# clockport_nic.net
KiCad netlist of a schematic drawn in EAGLE
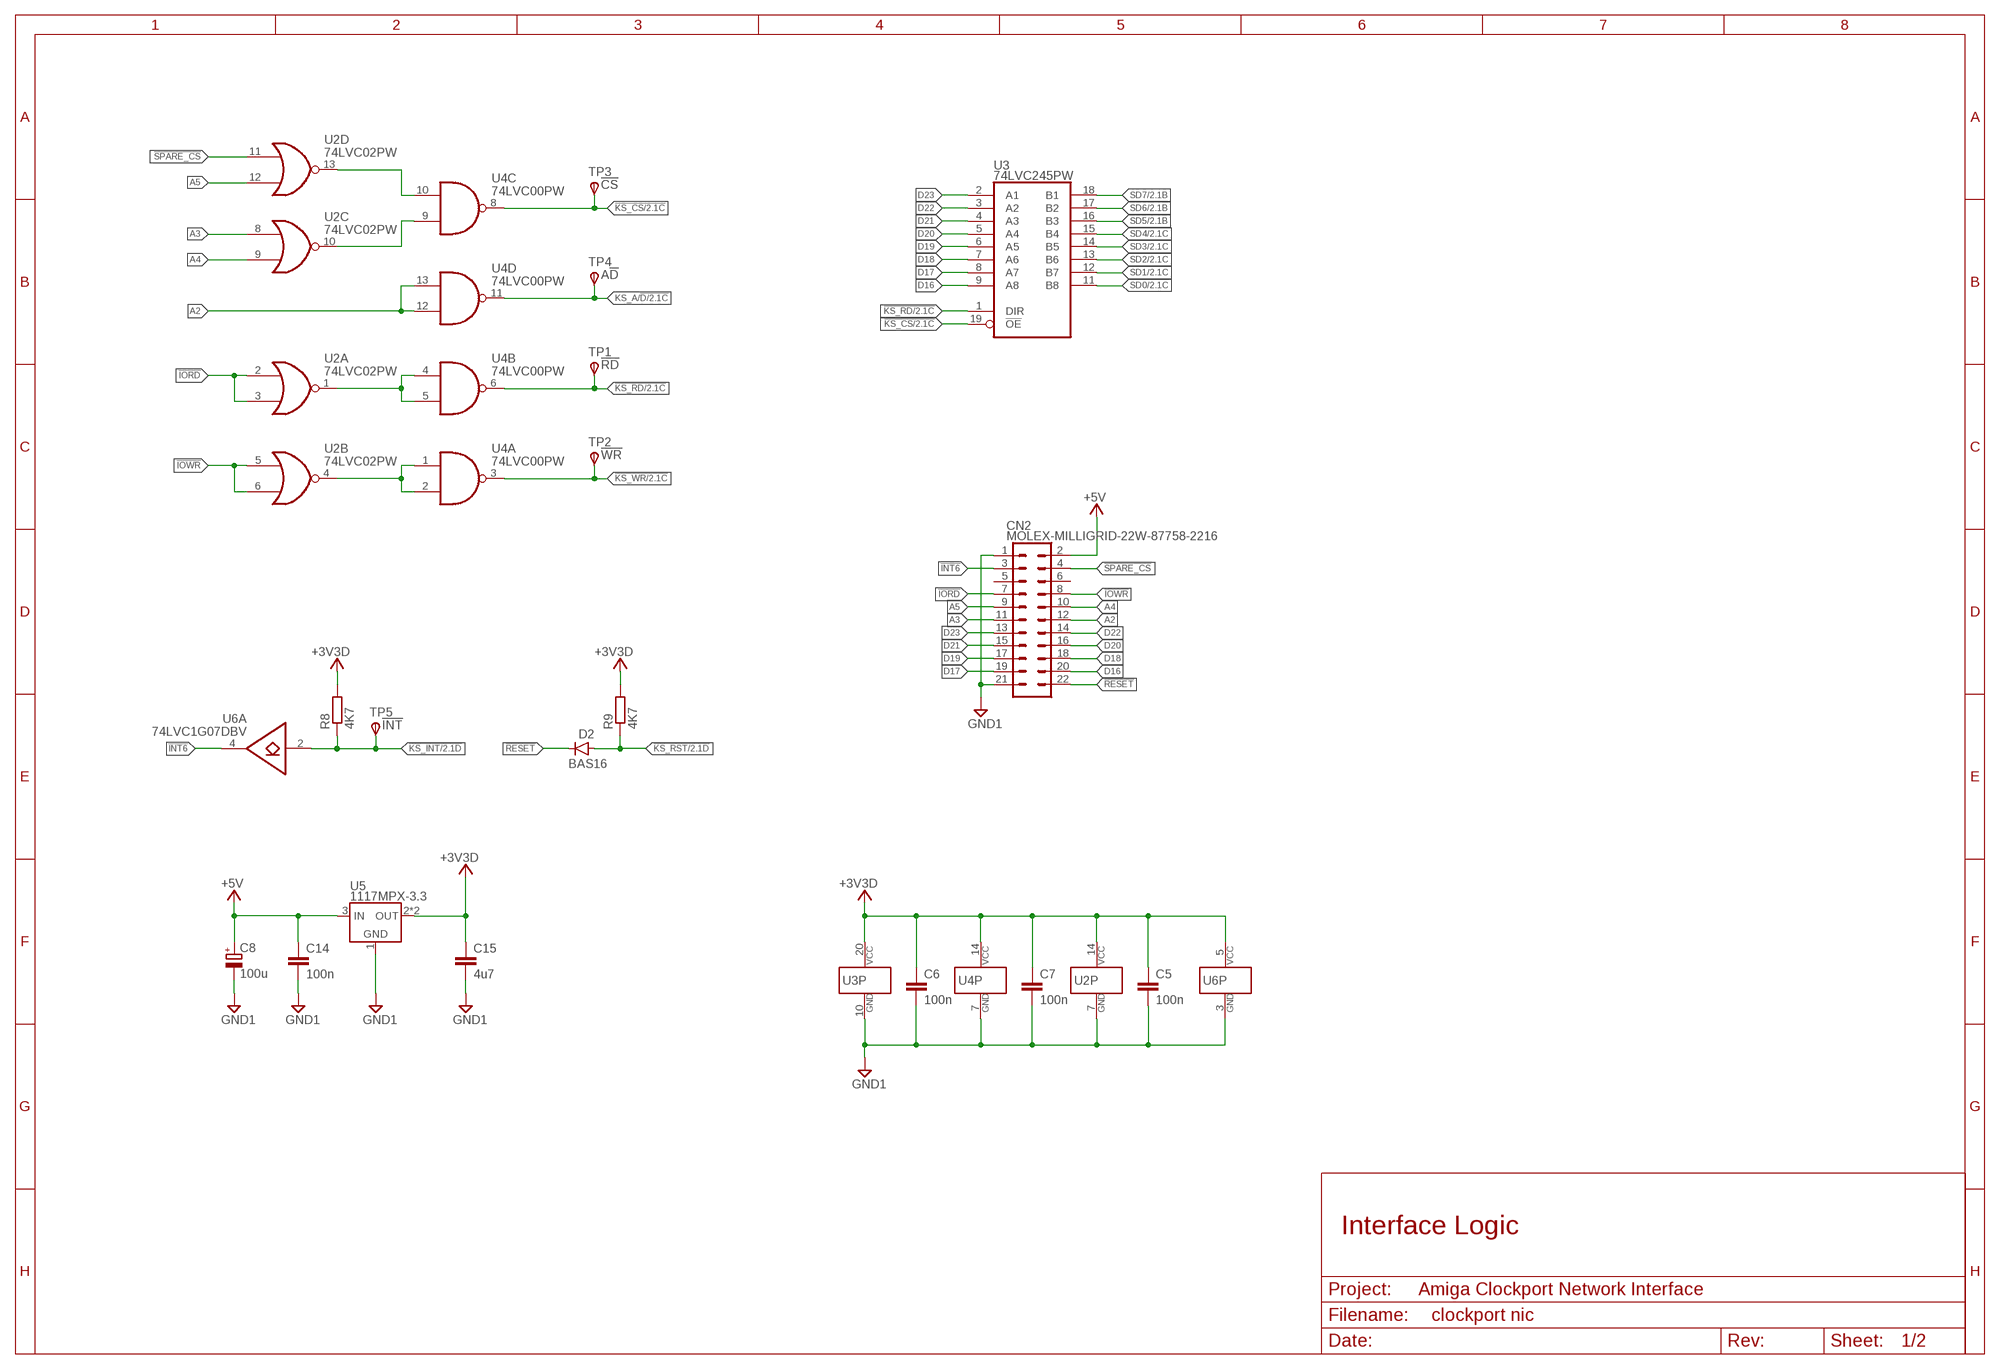
[diagram p0: schematic, sheet 1]
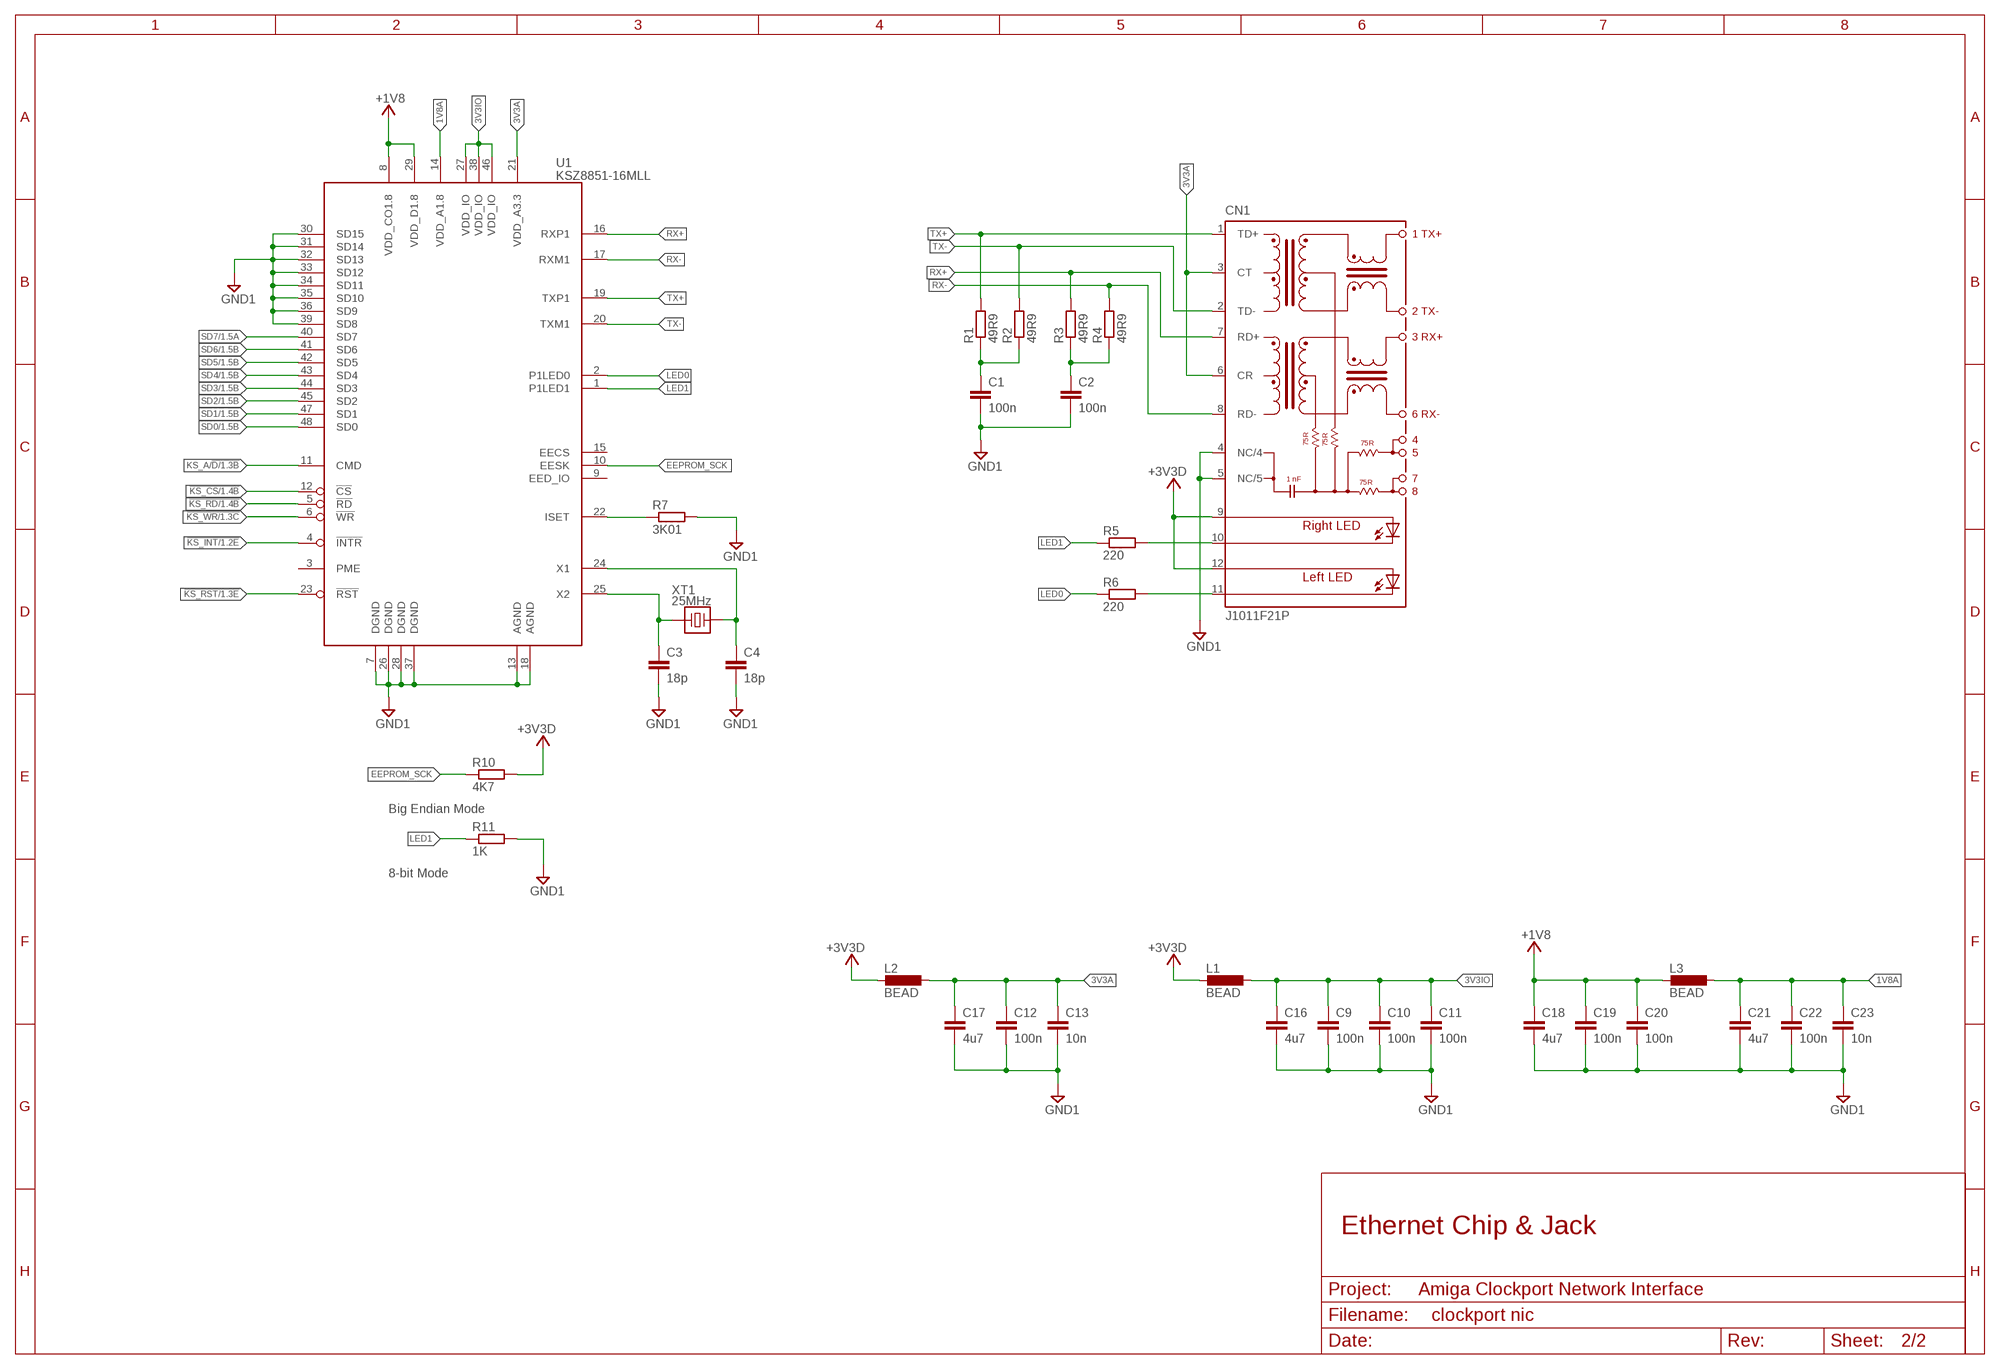
[diagram p1: schematic, sheet 2]

(export (version "E")
  (design (tool "Eeschema 10.0.6"))
  (components
    (comp (ref "C5")
      (value "100n")
      (footprint "eagle-import:C0603")
      (libsource (lib "eagle-import") (part "C-EUC0603"))
    )
    (comp (ref "C6")
      (value "100n")
      (footprint "eagle-import:C0603")
      (libsource (lib "eagle-import") (part "C-EUC0603"))
    )
    (comp (ref "C7")
      (value "100n")
      (footprint "eagle-import:C0603")
      (libsource (lib "eagle-import") (part "C-EUC0603"))
    )
    (comp (ref "C8")
      (value "100u")
      (footprint "eagle-import:E2,5-6")
      (libsource (lib "eagle-import") (part "CPOL-EUE2.5-6"))
    )
    (comp (ref "C14")
      (value "100n")
      (footprint "eagle-import:C0603")
      (libsource (lib "eagle-import") (part "C-EUC0603"))
    )
    (comp (ref "C15")
      (value "4u7")
      (footprint "eagle-import:C0805")
      (libsource (lib "eagle-import") (part "C-EUC0805"))
    )
    (comp (ref "CN2")
      (value "MOLEX-MILLIGRID-22W-87758-2216")
      (footprint "eagle-import:MOLEX-87758-2216")
      (libsource (lib "eagle-import") (part "MOLEX-MILLIGRID-22W-?87758-2216"))
    )
    (comp (ref "D2")
      (value "BAS16")
      (footprint "eagle-import:SOD323-R")
      (libsource (lib "eagle-import") (part "-DIODE_?SOD-323"))
    )
    (comp (ref "R8")
      (value "4K7")
      (footprint "eagle-import:R0603")
      (libsource (lib "eagle-import") (part "R-EU_R0603"))
    )
    (comp (ref "R9")
      (value "4K7")
      (footprint "eagle-import:R0603")
      (libsource (lib "eagle-import") (part "R-EU_R0603"))
    )
    (comp (ref "TP1")
      (value "TPSB1,27")
      (footprint "eagle-import:B1,27")
      (fields (field (name "TP_SIGNAL_NAME") "!RD"))
      (libsource (lib "eagle-import") (part "TPSB1,27"))
    )
    (comp (ref "TP2")
      (value "TPSB1,27")
      (footprint "eagle-import:B1,27")
      (fields (field (name "TP_SIGNAL_NAME") "!WR"))
      (libsource (lib "eagle-import") (part "TPSB1,27"))
    )
    (comp (ref "TP3")
      (value "TPSB1,27")
      (footprint "eagle-import:B1,27")
      (fields (field (name "TP_SIGNAL_NAME") "!CS"))
      (libsource (lib "eagle-import") (part "TPSB1,27"))
    )
    (comp (ref "TP4")
      (value "TPSB1,27")
      (footprint "eagle-import:B1,27")
      (fields (field (name "TP_SIGNAL_NAME") "A!D"))
      (libsource (lib "eagle-import") (part "TPSB1,27"))
    )
    (comp (ref "TP5")
      (value "TPSB1,27")
      (footprint "eagle-import:B1,27")
      (fields (field (name "TP_SIGNAL_NAME") "!INT"))
      (libsource (lib "eagle-import") (part "TPSB1,27"))
    )
    (comp (ref "U2")
      (value "74LVC02PW")
      (footprint "eagle-import:TSSOP14")
      (libsource (lib "eagle-import") (part "7402PWLVC"))
    )
    (comp (ref "U3")
      (value "74LVC245PW")
      (footprint "eagle-import:TSSOP20")
      (libsource (lib "eagle-import") (part "74245PWLVC"))
    )
    (comp (ref "U4")
      (value "74LVC00PW")
      (footprint "eagle-import:TSSOP14")
      (libsource (lib "eagle-import") (part "7400PWLVC"))
    )
    (comp (ref "U5")
      (value "1117MPX-3.3")
      (footprint "eagle-import:SOT223")
      (libsource (lib "eagle-import") (part "1117?-MPX3.3"))
    )
    (comp (ref "U6")
      (value "74LVC1G07DBV")
      (footprint "eagle-import:SOT23-5")
      (libsource (lib "eagle-import") (part "74LVC1G07DBV"))
    )
    (comp (ref "C1")
      (value "100n")
      (footprint "eagle-import:C0603")
      (libsource (lib "eagle-import") (part "C-EUC0603"))
    )
    (comp (ref "C2")
      (value "100n")
      (footprint "eagle-import:C0603")
      (libsource (lib "eagle-import") (part "C-EUC0603"))
    )
    (comp (ref "C3")
      (value "18p")
      (footprint "eagle-import:C0603")
      (libsource (lib "eagle-import") (part "C-EUC0603"))
    )
    (comp (ref "C4")
      (value "18p")
      (footprint "eagle-import:C0603")
      (libsource (lib "eagle-import") (part "C-EUC0603"))
    )
    (comp (ref "C9")
      (value "100n")
      (footprint "eagle-import:C0603")
      (libsource (lib "eagle-import") (part "C-EUC0603"))
    )
    (comp (ref "C10")
      (value "100n")
      (footprint "eagle-import:C0603")
      (libsource (lib "eagle-import") (part "C-EUC0603"))
    )
    (comp (ref "C11")
      (value "100n")
      (footprint "eagle-import:C0603")
      (libsource (lib "eagle-import") (part "C-EUC0603"))
    )
    (comp (ref "C12")
      (value "100n")
      (footprint "eagle-import:C0603")
      (libsource (lib "eagle-import") (part "C-EUC0603"))
    )
    (comp (ref "C13")
      (value "10n")
      (footprint "eagle-import:C0603")
      (libsource (lib "eagle-import") (part "C-EUC0603"))
    )
    (comp (ref "C16")
      (value "4u7")
      (footprint "eagle-import:C0805")
      (libsource (lib "eagle-import") (part "C-EUC0805"))
    )
    (comp (ref "C17")
      (value "4u7")
      (footprint "eagle-import:C0805")
      (libsource (lib "eagle-import") (part "C-EUC0805"))
    )
    (comp (ref "C18")
      (value "4u7")
      (footprint "eagle-import:C0805")
      (libsource (lib "eagle-import") (part "C-EUC0805"))
    )
    (comp (ref "C19")
      (value "100n")
      (footprint "eagle-import:C0603")
      (libsource (lib "eagle-import") (part "C-EUC0603"))
    )
    (comp (ref "C20")
      (value "100n")
      (footprint "eagle-import:C0603")
      (libsource (lib "eagle-import") (part "C-EUC0603"))
    )
    (comp (ref "C21")
      (value "4u7")
      (footprint "eagle-import:C0805")
      (libsource (lib "eagle-import") (part "C-EUC0805"))
    )
    (comp (ref "C22")
      (value "100n")
      (footprint "eagle-import:C0603")
      (libsource (lib "eagle-import") (part "C-EUC0603"))
    )
    (comp (ref "C23")
      (value "10n")
      (footprint "eagle-import:C0603")
      (libsource (lib "eagle-import") (part "C-EUC0603"))
    )
    (comp (ref "CN1")
      (value "J1011F21P")
      (footprint "eagle-import:J1")
      (libsource (lib "eagle-import") (part "J1011F21P"))
    )
    (comp (ref "L1")
      (value "BEAD")
      (footprint "eagle-import:L2012C")
      (libsource (lib "eagle-import") (part "L-EUL2012C"))
    )
    (comp (ref "L2")
      (value "BEAD")
      (footprint "eagle-import:L2012C")
      (libsource (lib "eagle-import") (part "L-EUL2012C"))
    )
    (comp (ref "L3")
      (value "BEAD")
      (footprint "eagle-import:L2012C")
      (libsource (lib "eagle-import") (part "L-EUL2012C"))
    )
    (comp (ref "R1")
      (value "49R9")
      (footprint "eagle-import:R0603")
      (libsource (lib "eagle-import") (part "R-EU_R0603"))
    )
    (comp (ref "R2")
      (value "49R9")
      (footprint "eagle-import:R0603")
      (libsource (lib "eagle-import") (part "R-EU_R0603"))
    )
    (comp (ref "R3")
      (value "49R9")
      (footprint "eagle-import:R0603")
      (libsource (lib "eagle-import") (part "R-EU_R0603"))
    )
    (comp (ref "R4")
      (value "49R9")
      (footprint "eagle-import:R0603")
      (libsource (lib "eagle-import") (part "R-EU_R0603"))
    )
    (comp (ref "R5")
      (value "220")
      (footprint "eagle-import:R0603")
      (libsource (lib "eagle-import") (part "R-EU_R0603"))
    )
    (comp (ref "R6")
      (value "220")
      (footprint "eagle-import:R0603")
      (libsource (lib "eagle-import") (part "R-EU_R0603"))
    )
    (comp (ref "R7")
      (value "3K01")
      (footprint "eagle-import:R0603")
      (libsource (lib "eagle-import") (part "R-EU_R0603"))
    )
    (comp (ref "R10")
      (value "4K7")
      (footprint "eagle-import:R0603")
      (libsource (lib "eagle-import") (part "R-EU_R0603"))
    )
    (comp (ref "R11")
      (value "1K")
      (footprint "eagle-import:R0603")
      (libsource (lib "eagle-import") (part "R-EU_R0603"))
    )
    (comp (ref "U1")
      (value "KSZ8851-16MLL")
      (footprint "eagle-import:LQFP48")
      (libsource (lib "eagle-import") (part "KSZ8851-16MLL"))
    )
    (comp (ref "XT1")
      (value "25MHz")
      (footprint "eagle-import:3225_4PAD")
      (libsource (lib "eagle-import") (part "XTAL_3225"))
    )
  )
  (nets
    (net (code "1") (name "+1V8") (class "Default")
      (node (ref "C18") (pin "1") (pinfunction "1_1") (pintype "passive"))
      (node (ref "C19") (pin "1") (pinfunction "1_1") (pintype "passive"))
      (node (ref "C20") (pin "1") (pinfunction "1_1") (pintype "passive"))
      (node (ref "L3") (pin "2") (pinfunction "2_2") (pintype "passive"))
      (node (ref "U1") (pin "29") (pinfunction "VDD_D1.8_29") (pintype "power_in"))
      (node (ref "U1") (pin "8") (pinfunction "VDD_CO1.8_8") (pintype "output"))
    )
    (net (code "2") (name "+3V3D") (class "Default")
      (node (ref "C15") (pin "1") (pinfunction "1_1") (pintype "passive"))
      (node (ref "C5") (pin "1") (pinfunction "1_1") (pintype "passive"))
      (node (ref "C6") (pin "1") (pinfunction "1_1") (pintype "passive"))
      (node (ref "C7") (pin "1") (pinfunction "1_1") (pintype "passive"))
      (node (ref "CN1") (pin "12") (pinfunction "AL_12") (pintype "passive"))
      (node (ref "CN1") (pin "9") (pinfunction "A-R_9") (pintype "passive"))
      (node (ref "L1") (pin "2") (pinfunction "2_2") (pintype "passive"))
      (node (ref "L2") (pin "2") (pinfunction "2_2") (pintype "passive"))
      (node (ref "R10") (pin "2") (pinfunction "2_2") (pintype "passive"))
      (node (ref "R8") (pin "2") (pinfunction "2_2") (pintype "passive"))
      (node (ref "R9") (pin "2") (pinfunction "2_2") (pintype "passive"))
      (node (ref "U2") (pin "14") (pinfunction "VCC_14") (pintype "power_in"))
      (node (ref "U3") (pin "20") (pinfunction "VCC_20") (pintype "power_in"))
      (node (ref "U4") (pin "14") (pinfunction "VCC_14") (pintype "power_in"))
      (node (ref "U5") (pin "2") (pinfunction "OUT_2") (pintype "passive"))
      (node (ref "U5") (pin "4") (pinfunction "OUT_4") (pintype "passive"))
      (node (ref "U6") (pin "5") (pinfunction "VCC_5") (pintype "power_in"))
    )
    (net (code "3") (name "+5V") (class "Default")
      (node (ref "C14") (pin "1") (pinfunction "1_1") (pintype "passive"))
      (node (ref "C8") (pin "+") (pinfunction "+_+") (pintype "passive"))
      (node (ref "CN2") (pin "2") (pinfunction "2_2") (pintype "passive"))
      (node (ref "U5") (pin "3") (pinfunction "IN_3") (pintype "passive"))
    )
    (net (code "4") (name "1V8A") (class "Default")
      (node (ref "C21") (pin "1") (pinfunction "1_1") (pintype "passive"))
      (node (ref "C22") (pin "1") (pinfunction "1_1") (pintype "passive"))
      (node (ref "C23") (pin "1") (pinfunction "1_1") (pintype "passive"))
      (node (ref "L3") (pin "1") (pinfunction "1_1") (pintype "passive"))
      (node (ref "U1") (pin "14") (pinfunction "VDD_A1.8_14") (pintype "power_in"))
    )
    (net (code "5") (name "3V3A") (class "Default")
      (node (ref "C12") (pin "1") (pinfunction "1_1") (pintype "passive"))
      (node (ref "C13") (pin "1") (pinfunction "1_1") (pintype "passive"))
      (node (ref "C17") (pin "1") (pinfunction "1_1") (pintype "passive"))
      (node (ref "CN1") (pin "3") (pinfunction "CT_3") (pintype "input"))
      (node (ref "CN1") (pin "6") (pinfunction "CR_6") (pintype "input"))
      (node (ref "L2") (pin "1") (pinfunction "1_1") (pintype "passive"))
      (node (ref "U1") (pin "21") (pinfunction "VDD_A3.3_21") (pintype "power_in"))
    )
    (net (code "6") (name "3V3IO") (class "Default")
      (node (ref "C10") (pin "1") (pinfunction "1_1") (pintype "passive"))
      (node (ref "C11") (pin "1") (pinfunction "1_1") (pintype "passive"))
      (node (ref "C16") (pin "1") (pinfunction "1_1") (pintype "passive"))
      (node (ref "C9") (pin "1") (pinfunction "1_1") (pintype "passive"))
      (node (ref "L1") (pin "1") (pinfunction "1_1") (pintype "passive"))
      (node (ref "U1") (pin "27") (pinfunction "VDD_IO_27") (pintype "power_in"))
      (node (ref "U1") (pin "38") (pinfunction "VDD_IO_38") (pintype "power_in"))
      (node (ref "U1") (pin "46") (pinfunction "VDD_IO_46") (pintype "power_in"))
    )
    (net (code "7") (name "A2") (class "Default")
      (node (ref "CN2") (pin "12") (pinfunction "12_12") (pintype "passive"))
      (node (ref "U4") (pin "12") (pinfunction "I1_12") (pintype "input"))
      (node (ref "U4") (pin "13") (pinfunction "I0_13") (pintype "input"))
    )
    (net (code "8") (name "A3") (class "Default")
      (node (ref "CN2") (pin "11") (pinfunction "11_11") (pintype "passive"))
      (node (ref "U2") (pin "8") (pinfunction "I0_8") (pintype "input"))
    )
    (net (code "9") (name "A4") (class "Default")
      (node (ref "CN2") (pin "10") (pinfunction "10_10") (pintype "passive"))
      (node (ref "U2") (pin "9") (pinfunction "I1_9") (pintype "input"))
    )
    (net (code "10") (name "A5") (class "Default")
      (node (ref "CN2") (pin "9") (pinfunction "9_9") (pintype "passive"))
      (node (ref "U2") (pin "12") (pinfunction "I1_12") (pintype "input"))
    )
    (net (code "11") (name "D16") (class "Default")
      (node (ref "CN2") (pin "20") (pinfunction "20_20") (pintype "passive"))
      (node (ref "U3") (pin "9") (pinfunction "A8_9") (pintype "bidirectional"))
    )
    (net (code "12") (name "D17") (class "Default")
      (node (ref "CN2") (pin "19") (pinfunction "19_19") (pintype "passive"))
      (node (ref "U3") (pin "8") (pinfunction "A7_8") (pintype "bidirectional"))
    )
    (net (code "13") (name "D18") (class "Default")
      (node (ref "CN2") (pin "18") (pinfunction "18_18") (pintype "passive"))
      (node (ref "U3") (pin "7") (pinfunction "A6_7") (pintype "bidirectional"))
    )
    (net (code "14") (name "D19") (class "Default")
      (node (ref "CN2") (pin "17") (pinfunction "17_17") (pintype "passive"))
      (node (ref "U3") (pin "6") (pinfunction "A5_6") (pintype "bidirectional"))
    )
    (net (code "15") (name "D20") (class "Default")
      (node (ref "CN2") (pin "16") (pinfunction "16_16") (pintype "passive"))
      (node (ref "U3") (pin "5") (pinfunction "A4_5") (pintype "bidirectional"))
    )
    (net (code "16") (name "D21") (class "Default")
      (node (ref "CN2") (pin "15") (pinfunction "15_15") (pintype "passive"))
      (node (ref "U3") (pin "4") (pinfunction "A3_4") (pintype "bidirectional"))
    )
    (net (code "17") (name "D22") (class "Default")
      (node (ref "CN2") (pin "14") (pinfunction "14_14") (pintype "passive"))
      (node (ref "U3") (pin "3") (pinfunction "A2_3") (pintype "bidirectional"))
    )
    (net (code "18") (name "D23") (class "Default")
      (node (ref "CN2") (pin "13") (pinfunction "13_13") (pintype "passive"))
      (node (ref "U3") (pin "2") (pinfunction "A1_2") (pintype "bidirectional"))
    )
    (net (code "19") (name "EEPROM_SCK") (class "Default")
      (node (ref "R10") (pin "1") (pinfunction "1_1") (pintype "passive"))
      (node (ref "U1") (pin "10") (pinfunction "EESK_10") (pintype "output"))
    )
    (net (code "20") (name "GND1") (class "Default")
      (node (ref "C1") (pin "2") (pinfunction "2_2") (pintype "passive"))
      (node (ref "C10") (pin "2") (pinfunction "2_2") (pintype "passive"))
      (node (ref "C11") (pin "2") (pinfunction "2_2") (pintype "passive"))
      (node (ref "C12") (pin "2") (pinfunction "2_2") (pintype "passive"))
      (node (ref "C13") (pin "2") (pinfunction "2_2") (pintype "passive"))
      (node (ref "C14") (pin "2") (pinfunction "2_2") (pintype "passive"))
      (node (ref "C15") (pin "2") (pinfunction "2_2") (pintype "passive"))
      (node (ref "C16") (pin "2") (pinfunction "2_2") (pintype "passive"))
      (node (ref "C17") (pin "2") (pinfunction "2_2") (pintype "passive"))
      (node (ref "C18") (pin "2") (pinfunction "2_2") (pintype "passive"))
      (node (ref "C19") (pin "2") (pinfunction "2_2") (pintype "passive"))
      (node (ref "C2") (pin "2") (pinfunction "2_2") (pintype "passive"))
      (node (ref "C20") (pin "2") (pinfunction "2_2") (pintype "passive"))
      (node (ref "C21") (pin "2") (pinfunction "2_2") (pintype "passive"))
      (node (ref "C22") (pin "2") (pinfunction "2_2") (pintype "passive"))
      (node (ref "C23") (pin "2") (pinfunction "2_2") (pintype "passive"))
      (node (ref "C3") (pin "2") (pinfunction "2_2") (pintype "passive"))
      (node (ref "C4") (pin "2") (pinfunction "2_2") (pintype "passive"))
      (node (ref "C5") (pin "2") (pinfunction "2_2") (pintype "passive"))
      (node (ref "C6") (pin "2") (pinfunction "2_2") (pintype "passive"))
      (node (ref "C7") (pin "2") (pinfunction "2_2") (pintype "passive"))
      (node (ref "C8") (pin "-") (pinfunction "-_-") (pintype "passive"))
      (node (ref "C9") (pin "2") (pinfunction "2_2") (pintype "passive"))
      (node (ref "CN1") (pin "4") (pinfunction "NC/4_4") (pintype "input"))
      (node (ref "CN1") (pin "5") (pinfunction "NC/5_5") (pintype "input"))
      (node (ref "CN2") (pin "1") (pinfunction "1_1") (pintype "passive"))
      (node (ref "CN2") (pin "21") (pinfunction "21_21") (pintype "passive"))
      (node (ref "R11") (pin "2") (pinfunction "2_2") (pintype "passive"))
      (node (ref "R7") (pin "2") (pinfunction "2_2") (pintype "passive"))
      (node (ref "U1") (pin "13") (pinfunction "AGND_13") (pintype "power_in"))
      (node (ref "U1") (pin "18") (pinfunction "AGND_18") (pintype "power_in"))
      (node (ref "U1") (pin "26") (pinfunction "DGND_26") (pintype "power_in"))
      (node (ref "U1") (pin "28") (pinfunction "DGND_28") (pintype "power_in"))
      (node (ref "U1") (pin "30") (pinfunction "SD15_30") (pintype "bidirectional"))
      (node (ref "U1") (pin "31") (pinfunction "SD14_31") (pintype "bidirectional"))
      (node (ref "U1") (pin "32") (pinfunction "SD13_32") (pintype "bidirectional"))
      (node (ref "U1") (pin "33") (pinfunction "SD12_33") (pintype "bidirectional"))
      (node (ref "U1") (pin "34") (pinfunction "SD11_34") (pintype "bidirectional"))
      (node (ref "U1") (pin "35") (pinfunction "SD10_35") (pintype "bidirectional"))
      (node (ref "U1") (pin "36") (pinfunction "SD9_36") (pintype "bidirectional"))
      (node (ref "U1") (pin "37") (pinfunction "DGND_37") (pintype "power_in"))
      (node (ref "U1") (pin "39") (pinfunction "SD8_39") (pintype "bidirectional"))
      (node (ref "U1") (pin "7") (pinfunction "DGND_7") (pintype "power_in"))
      (node (ref "U2") (pin "7") (pinfunction "GND_7") (pintype "power_in"))
      (node (ref "U3") (pin "10") (pinfunction "GND_10") (pintype "power_in"))
      (node (ref "U4") (pin "7") (pinfunction "GND_7") (pintype "power_in"))
      (node (ref "U5") (pin "1") (pinfunction "GND_1") (pintype "passive"))
      (node (ref "U6") (pin "3") (pinfunction "GND_3") (pintype "power_in"))
    )
    (net (code "21") (name "KS_A{slash}~{D}") (class "Default")
      (node (ref "TP4") (pin "TP") (pinfunction "PP_TP") (pintype "input"))
      (node (ref "U1") (pin "11") (pinfunction "CMD_11") (pintype "input"))
      (node (ref "U4") (pin "11") (pinfunction "O_11") (pintype "output"))
    )
    (net (code "22") (name "LED0") (class "Default")
      (node (ref "R6") (pin "1") (pinfunction "1_1") (pintype "passive"))
      (node (ref "U1") (pin "2") (pinfunction "P1LED0_2") (pintype "output"))
    )
    (net (code "23") (name "LED1") (class "Default")
      (node (ref "R11") (pin "1") (pinfunction "1_1") (pintype "passive"))
      (node (ref "R5") (pin "1") (pinfunction "1_1") (pintype "passive"))
      (node (ref "U1") (pin "1") (pinfunction "P1LED1_1") (pintype "output"))
    )
    (net (code "24") (name "Net-(C1-Pad1)") (class "Default")
      (node (ref "C1") (pin "1") (pinfunction "1_1") (pintype "passive"))
      (node (ref "R1") (pin "1") (pinfunction "1_1") (pintype "passive"))
      (node (ref "R2") (pin "1") (pinfunction "1_1") (pintype "passive"))
    )
    (net (code "25") (name "Net-(C2-Pad1)") (class "Default")
      (node (ref "C2") (pin "1") (pinfunction "1_1") (pintype "passive"))
      (node (ref "R3") (pin "1") (pinfunction "1_1") (pintype "passive"))
      (node (ref "R4") (pin "1") (pinfunction "1_1") (pintype "passive"))
    )
    (net (code "26") (name "Net-(CN1-C-L)") (class "Default")
      (node (ref "CN1") (pin "11") (pinfunction "C-L_11") (pintype "passive"))
      (node (ref "R6") (pin "2") (pinfunction "2_2") (pintype "passive"))
    )
    (net (code "27") (name "Net-(CN1-C-R)") (class "Default")
      (node (ref "CN1") (pin "10") (pinfunction "C-R_10") (pintype "passive"))
      (node (ref "R5") (pin "2") (pinfunction "2_2") (pintype "passive"))
    )
    (net (code "28") (name "Net-(U1-ISET)") (class "Default")
      (node (ref "R7") (pin "1") (pinfunction "1_1") (pintype "passive"))
      (node (ref "U1") (pin "22") (pinfunction "ISET_22") (pintype "passive"))
    )
    (net (code "29") (name "Net-(U1-X1)") (class "Default")
      (node (ref "C4") (pin "1") (pinfunction "1_1") (pintype "passive"))
      (node (ref "U1") (pin "24") (pinfunction "X1_24") (pintype "passive"))
      (node (ref "XT1") (pin "3") (pinfunction "2_3") (pintype "passive"))
    )
    (net (code "30") (name "Net-(U1-X2)") (class "Default")
      (node (ref "C3") (pin "1") (pinfunction "1_1") (pintype "passive"))
      (node (ref "U1") (pin "25") (pinfunction "X2_25") (pintype "passive"))
      (node (ref "XT1") (pin "1") (pinfunction "1_1") (pintype "passive"))
    )
    (net (code "31") (name "Net-(U2A-O)") (class "Default")
      (node (ref "U2") (pin "1") (pinfunction "O_1") (pintype "output"))
      (node (ref "U4") (pin "4") (pinfunction "I0_4") (pintype "input"))
      (node (ref "U4") (pin "5") (pinfunction "I1_5") (pintype "input"))
    )
    (net (code "32") (name "Net-(U2B-O)") (class "Default")
      (node (ref "U2") (pin "4") (pinfunction "O_4") (pintype "output"))
      (node (ref "U4") (pin "1") (pinfunction "I0_1") (pintype "input"))
      (node (ref "U4") (pin "2") (pinfunction "I1_2") (pintype "input"))
    )
    (net (code "33") (name "Net-(U2C-O)") (class "Default")
      (node (ref "U2") (pin "10") (pinfunction "O_10") (pintype "output"))
      (node (ref "U4") (pin "9") (pinfunction "I1_9") (pintype "input"))
    )
    (net (code "34") (name "Net-(U2D-O)") (class "Default")
      (node (ref "U2") (pin "13") (pinfunction "O_13") (pintype "output"))
      (node (ref "U4") (pin "10") (pinfunction "I0_10") (pintype "input"))
    )
    (net (code "35") (name "RX+") (class "Default")
      (node (ref "CN1") (pin "7") (pinfunction "RD+_7") (pintype "input"))
      (node (ref "R3") (pin "2") (pinfunction "2_2") (pintype "passive"))
      (node (ref "U1") (pin "16") (pinfunction "RXP1_16") (pintype "passive"))
    )
    (net (code "36") (name "RX-") (class "Default")
      (node (ref "CN1") (pin "8") (pinfunction "RD-_8") (pintype "input"))
      (node (ref "R4") (pin "2") (pinfunction "2_2") (pintype "passive"))
      (node (ref "U1") (pin "17") (pinfunction "RXM1_17") (pintype "passive"))
    )
    (net (code "37") (name "SD0") (class "Default")
      (node (ref "U1") (pin "48") (pinfunction "SD0_48") (pintype "bidirectional"))
      (node (ref "U3") (pin "11") (pinfunction "B8_11") (pintype "bidirectional"))
    )
    (net (code "38") (name "SD1") (class "Default")
      (node (ref "U1") (pin "47") (pinfunction "SD1_47") (pintype "bidirectional"))
      (node (ref "U3") (pin "12") (pinfunction "B7_12") (pintype "bidirectional"))
    )
    (net (code "39") (name "SD2") (class "Default")
      (node (ref "U1") (pin "45") (pinfunction "SD2_45") (pintype "bidirectional"))
      (node (ref "U3") (pin "13") (pinfunction "B6_13") (pintype "bidirectional"))
    )
    (net (code "40") (name "SD3") (class "Default")
      (node (ref "U1") (pin "44") (pinfunction "SD3_44") (pintype "bidirectional"))
      (node (ref "U3") (pin "14") (pinfunction "B5_14") (pintype "bidirectional"))
    )
    (net (code "41") (name "SD4") (class "Default")
      (node (ref "U1") (pin "43") (pinfunction "SD4_43") (pintype "bidirectional"))
      (node (ref "U3") (pin "15") (pinfunction "B4_15") (pintype "bidirectional"))
    )
    (net (code "42") (name "SD5") (class "Default")
      (node (ref "U1") (pin "42") (pinfunction "SD5_42") (pintype "bidirectional"))
      (node (ref "U3") (pin "16") (pinfunction "B3_16") (pintype "bidirectional"))
    )
    (net (code "43") (name "SD6") (class "Default")
      (node (ref "U1") (pin "41") (pinfunction "SD6_41") (pintype "bidirectional"))
      (node (ref "U3") (pin "17") (pinfunction "B2_17") (pintype "bidirectional"))
    )
    (net (code "44") (name "SD7") (class "Default")
      (node (ref "U1") (pin "40") (pinfunction "SD7_40") (pintype "bidirectional"))
      (node (ref "U3") (pin "18") (pinfunction "B1_18") (pintype "bidirectional"))
    )
    (net (code "45") (name "TX+") (class "Default")
      (node (ref "CN1") (pin "1") (pinfunction "TD+_1") (pintype "input"))
      (node (ref "R1") (pin "2") (pinfunction "2_2") (pintype "passive"))
      (node (ref "U1") (pin "19") (pinfunction "TXP1_19") (pintype "passive"))
    )
    (net (code "46") (name "TX-") (class "Default")
      (node (ref "CN1") (pin "2") (pinfunction "TD-_2") (pintype "input"))
      (node (ref "R2") (pin "2") (pinfunction "2_2") (pintype "passive"))
      (node (ref "U1") (pin "20") (pinfunction "TXM1_20") (pintype "passive"))
    )
    (net (code "47") (name "unconnected-(CN2-Pad5)") (class "Default")
      (node (ref "CN2") (pin "5") (pinfunction "5_5") (pintype "passive"))
    )
    (net (code "48") (name "unconnected-(CN2-Pad6)") (class "Default")
      (node (ref "CN2") (pin "6") (pinfunction "6_6") (pintype "passive"))
    )
    (net (code "49") (name "unconnected-(U1-EECS-Pad15)") (class "Default")
      (node (ref "U1") (pin "15") (pinfunction "EECS_15") (pintype "output"))
    )
    (net (code "50") (name "unconnected-(U1-EED_IO-Pad9)") (class "Default")
      (node (ref "U1") (pin "9") (pinfunction "EED_IO_9") (pintype "output"))
    )
    (net (code "51") (name "unconnected-(U1-PME-Pad3)") (class "Default")
      (node (ref "U1") (pin "3") (pinfunction "PME_3") (pintype "input"))
    )
    (net (code "52") (name "~{INT6}") (class "Default")
      (node (ref "CN2") (pin "3") (pinfunction "3_3") (pintype "passive"))
      (node (ref "U6") (pin "4") (pinfunction "O_4") (pintype "output"))
    )
    (net (code "53") (name "~{IORD}") (class "Default")
      (node (ref "CN2") (pin "7") (pinfunction "7_7") (pintype "passive"))
      (node (ref "U2") (pin "2") (pinfunction "I0_2") (pintype "input"))
      (node (ref "U2") (pin "3") (pinfunction "I1_3") (pintype "input"))
    )
    (net (code "54") (name "~{IOWR}") (class "Default")
      (node (ref "CN2") (pin "8") (pinfunction "8_8") (pintype "passive"))
      (node (ref "U2") (pin "5") (pinfunction "I0_5") (pintype "input"))
      (node (ref "U2") (pin "6") (pinfunction "I1_6") (pintype "input"))
    )
    (net (code "55") (name "~{KS_CS}") (class "Default")
      (node (ref "TP3") (pin "TP") (pinfunction "PP_TP") (pintype "input"))
      (node (ref "U1") (pin "12") (pinfunction "~{CS}_12") (pintype "input"))
      (node (ref "U3") (pin "19") (pinfunction "~{OE}_19") (pintype "input"))
      (node (ref "U4") (pin "8") (pinfunction "O_8") (pintype "output"))
    )
    (net (code "56") (name "~{KS_INT}") (class "Default")
      (node (ref "R8") (pin "1") (pinfunction "1_1") (pintype "passive"))
      (node (ref "TP5") (pin "TP") (pinfunction "PP_TP") (pintype "input"))
      (node (ref "U1") (pin "4") (pinfunction "~{INTR}_4") (pintype "output"))
      (node (ref "U6") (pin "2") (pinfunction "I_2") (pintype "input"))
    )
    (net (code "57") (name "~{KS_RD}") (class "Default")
      (node (ref "TP1") (pin "TP") (pinfunction "PP_TP") (pintype "input"))
      (node (ref "U1") (pin "5") (pinfunction "~{RD}_5") (pintype "input"))
      (node (ref "U3") (pin "1") (pinfunction "DIR_1") (pintype "input"))
      (node (ref "U4") (pin "6") (pinfunction "O_6") (pintype "output"))
    )
    (net (code "58") (name "~{KS_RST}") (class "Default")
      (node (ref "D2") (pin "A") (pinfunction "A_A") (pintype "passive"))
      (node (ref "R9") (pin "1") (pinfunction "1_1") (pintype "passive"))
      (node (ref "U1") (pin "23") (pinfunction "~{RST}_23") (pintype "input"))
    )
    (net (code "59") (name "~{KS_WR}") (class "Default")
      (node (ref "TP2") (pin "TP") (pinfunction "PP_TP") (pintype "input"))
      (node (ref "U1") (pin "6") (pinfunction "~{WR}_6") (pintype "input"))
      (node (ref "U4") (pin "3") (pinfunction "O_3") (pintype "output"))
    )
    (net (code "60") (name "~{RESET}") (class "Default")
      (node (ref "CN2") (pin "22") (pinfunction "22_22") (pintype "passive"))
      (node (ref "D2") (pin "K") (pinfunction "C_K") (pintype "passive"))
    )
    (net (code "61") (name "~{SPARE_CS}") (class "Default")
      (node (ref "CN2") (pin "4") (pinfunction "4_4") (pintype "passive"))
      (node (ref "U2") (pin "11") (pinfunction "I0_11") (pintype "input"))
    )
  )
)
